# brd.net
KiCad netlist of a schematic drawn in EAGLE
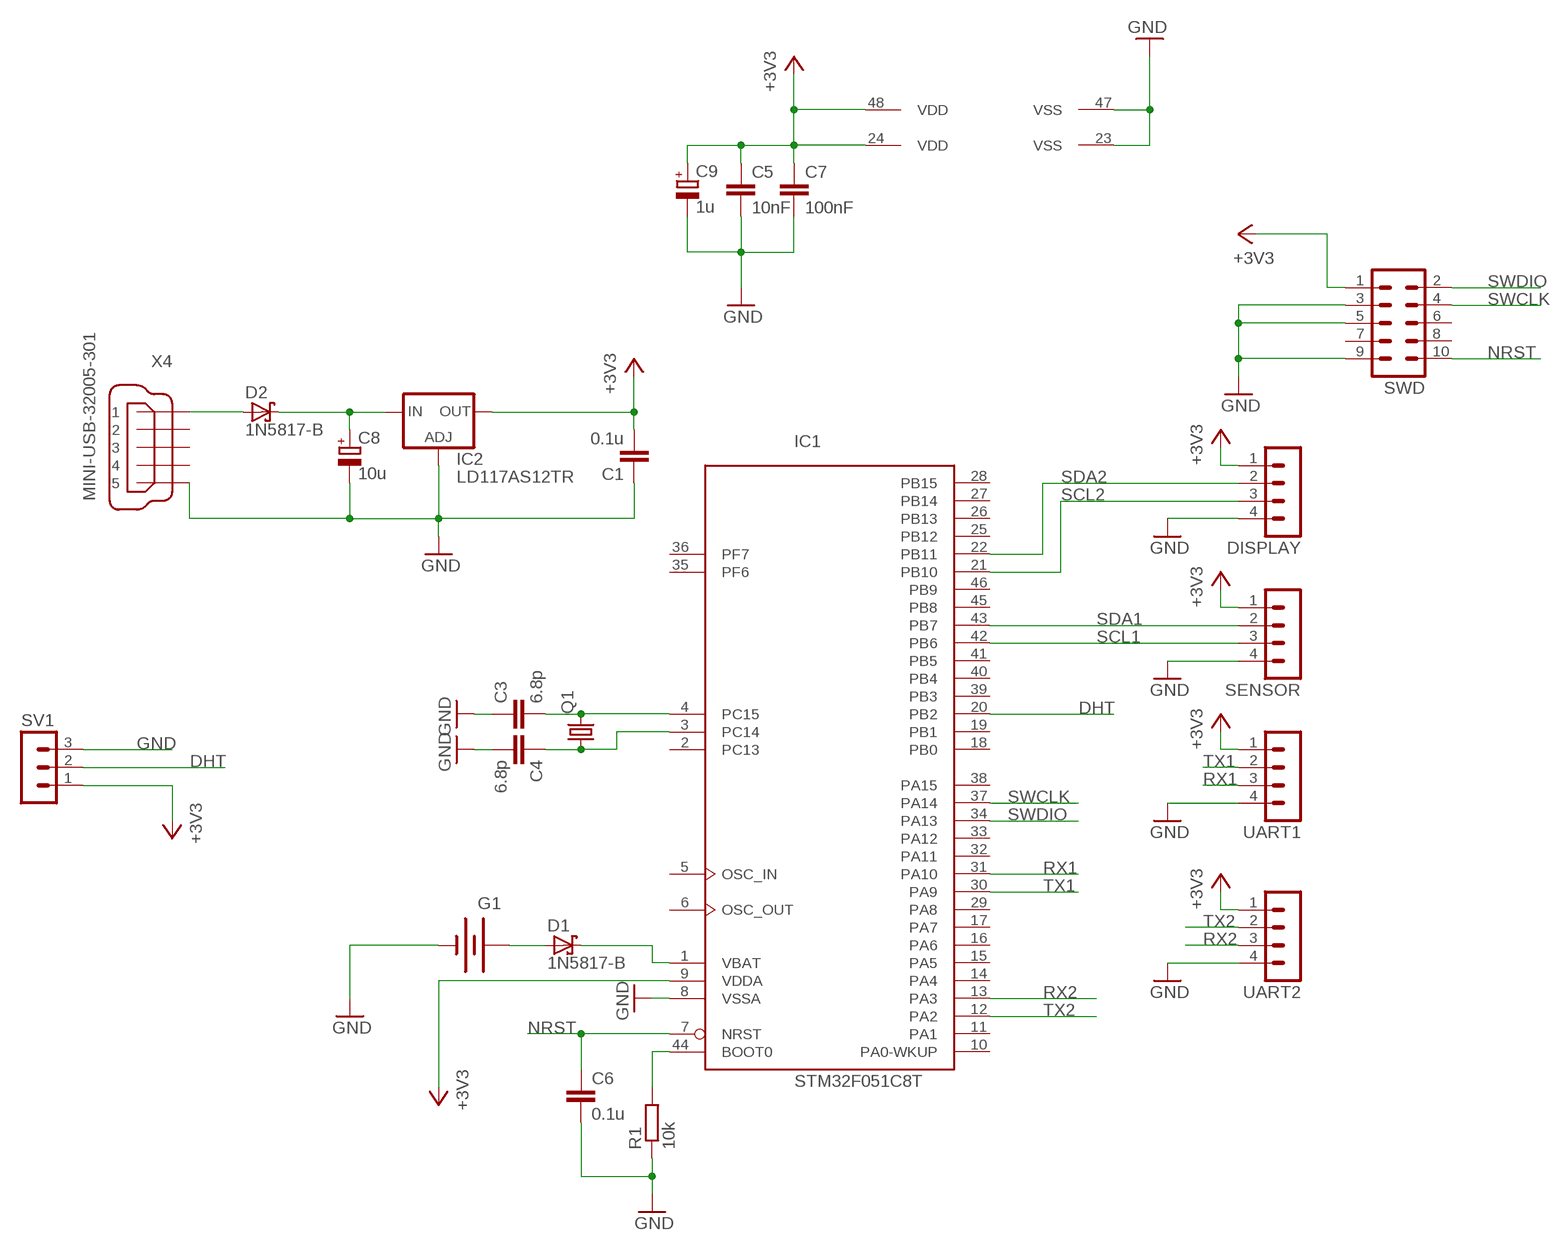
[diagram p0: schematic, sheet 1]

(export (version "E")
  (design (tool "Eeschema 10.0.6"))
  (components
    (comp (ref "C1")
      (value "0.1u")
      (footprint "eagle-import:C025-024X044")
      (libsource (lib "eagle-import") (part "C-EU025-024X044"))
    )
    (comp (ref "C3")
      (value "6.8p")
      (footprint "eagle-import:C0805")
      (libsource (lib "eagle-import") (part "C-EUC0805"))
    )
    (comp (ref "C4")
      (value "6.8p")
      (footprint "eagle-import:C0805")
      (libsource (lib "eagle-import") (part "C-EUC0805"))
    )
    (comp (ref "C5")
      (value "10nF")
      (footprint "eagle-import:C0805")
      (libsource (lib "eagle-import") (part "C-EUC0805"))
    )
    (comp (ref "C6")
      (value "0.1u")
      (footprint "eagle-import:C0805")
      (libsource (lib "eagle-import") (part "C-EUC0805"))
    )
    (comp (ref "C7")
      (value "100nF")
      (footprint "eagle-import:C0805")
      (libsource (lib "eagle-import") (part "C-EUC0805"))
    )
    (comp (ref "C8")
      (value "10u")
      (footprint "eagle-import:E2,5-6E")
      (libsource (lib "eagle-import") (part "CPOL-EUE2,5-6E"))
    )
    (comp (ref "C9")
      (value "1u")
      (footprint "eagle-import:E2,5-6E")
      (libsource (lib "eagle-import") (part "CPOL-EUE2,5-6E"))
    )
    (comp (ref "D1")
      (value "1N5817-B")
      (footprint "eagle-import:DO41-7.6")
      (libsource (lib "eagle-import") (part "1N5817-B"))
    )
    (comp (ref "D2")
      (value "1N5817-B")
      (footprint "eagle-import:DO41-7.6")
      (libsource (lib "eagle-import") (part "1N5817-B"))
    )
    (comp (ref "DISPLAY")
      (value "MA04-1")
      (footprint "eagle-import:MA04-1")
      (libsource (lib "eagle-import") (part "MA04-1"))
    )
    (comp (ref "G1")
      (value "BATTERY20PTH")
      (footprint "eagle-import:BATTCOM_20MM_PTH")
      (libsource (lib "eagle-import") (part "BATTERY20PTH"))
    )
    (comp (ref "IC1")
      (value "STM32F051C8T")
      (footprint "eagle-import:LQFP48")
      (libsource (lib "eagle-import") (part "STM32F051CT8"))
    )
    (comp (ref "IC2")
      (value "LD117AS12TR")
      (footprint "eagle-import:SOT223")
      (libsource (lib "eagle-import") (part "LD117A?S12TR"))
    )
    (comp (ref "Q1")
      (value "CRYSTALTC26H")
      (footprint "eagle-import:TC26H")
      (libsource (lib "eagle-import") (part "CRYSTALTC26H"))
    )
    (comp (ref "R1")
      (value "10k")
      (footprint "eagle-import:R0805")
      (libsource (lib "eagle-import") (part "R-EU_R0805"))
    )
    (comp (ref "SENSOR")
      (value "MA04-1")
      (footprint "eagle-import:MA04-1")
      (libsource (lib "eagle-import") (part "MA04-1"))
    )
    (comp (ref "SV1")
      (value "MA03-1")
      (footprint "eagle-import:MA03-1")
      (libsource (lib "eagle-import") (part "MA03-1"))
    )
    (comp (ref "SWD")
      (value "MA05-2")
      (footprint "eagle-import:MA05-2")
      (libsource (lib "eagle-import") (part "MA05-2"))
    )
    (comp (ref "UART1")
      (value "MA04-1")
      (footprint "eagle-import:MA04-1")
      (libsource (lib "eagle-import") (part "MA04-1"))
    )
    (comp (ref "UART2")
      (value "MA04-1")
      (footprint "eagle-import:MA04-1")
      (libsource (lib "eagle-import") (part "MA04-1"))
    )
    (comp (ref "X4")
      (value "MINI-USB-32005-301")
      (footprint "eagle-import:32005-301")
      (libsource (lib "eagle-import") (part "MINI-USB-32005-301"))
    )
  )
  (nets
    (net (code "1") (name "+3V3") (class "Default")
      (node (ref "C1") (pin "2") (pinfunction "2_2") (pintype "passive"))
      (node (ref "C5") (pin "1") (pinfunction "1_1") (pintype "passive"))
      (node (ref "C7") (pin "1") (pinfunction "1_1") (pintype "passive"))
      (node (ref "C9") (pin "+") (pinfunction "+_+") (pintype "passive"))
      (node (ref "DISPLAY") (pin "1") (pinfunction "1_1") (pintype "passive"))
      (node (ref "IC1") (pin "24") (pinfunction "VDD_24") (pintype "power_in"))
      (node (ref "IC1") (pin "48") (pinfunction "VDD_48") (pintype "power_in"))
      (node (ref "IC1") (pin "9") (pinfunction "VDDA_9") (pintype "power_in"))
      (node (ref "IC2") (pin "4") (pinfunction "OUT_4") (pintype "passive"))
      (node (ref "SENSOR") (pin "1") (pinfunction "1_1") (pintype "passive"))
      (node (ref "SV1") (pin "1") (pinfunction "1_1") (pintype "passive"))
      (node (ref "SWD") (pin "1") (pinfunction "1_1") (pintype "passive"))
      (node (ref "UART1") (pin "1") (pinfunction "1_1") (pintype "passive"))
      (node (ref "UART2") (pin "1") (pinfunction "1_1") (pintype "passive"))
    )
    (net (code "2") (name "/DHT") (class "Default")
      (node (ref "IC1") (pin "20") (pinfunction "PB2_20") (pintype "bidirectional"))
      (node (ref "SV1") (pin "2") (pinfunction "2_2") (pintype "passive"))
    )
    (net (code "3") (name "/NRST") (class "Default")
      (node (ref "C6") (pin "1") (pinfunction "1_1") (pintype "passive"))
      (node (ref "IC1") (pin "7") (pinfunction "NRST_7") (pintype "bidirectional"))
      (node (ref "SWD") (pin "10") (pinfunction "10_10") (pintype "passive"))
    )
    (net (code "4") (name "/RX1") (class "Default")
      (node (ref "IC1") (pin "31") (pinfunction "PA10_31") (pintype "bidirectional"))
      (node (ref "UART1") (pin "3") (pinfunction "3_3") (pintype "passive"))
    )
    (net (code "5") (name "/RX2") (class "Default")
      (node (ref "IC1") (pin "13") (pinfunction "PA3_13") (pintype "bidirectional"))
      (node (ref "UART2") (pin "3") (pinfunction "3_3") (pintype "passive"))
    )
    (net (code "6") (name "/SCL1") (class "Default")
      (node (ref "IC1") (pin "42") (pinfunction "PB6_42") (pintype "bidirectional"))
      (node (ref "SENSOR") (pin "3") (pinfunction "3_3") (pintype "passive"))
    )
    (net (code "7") (name "/SCL2") (class "Default")
      (node (ref "DISPLAY") (pin "3") (pinfunction "3_3") (pintype "passive"))
      (node (ref "IC1") (pin "21") (pinfunction "PB10_21") (pintype "bidirectional"))
    )
    (net (code "8") (name "/SDA1") (class "Default")
      (node (ref "IC1") (pin "43") (pinfunction "PB7_43") (pintype "bidirectional"))
      (node (ref "SENSOR") (pin "2") (pinfunction "2_2") (pintype "passive"))
    )
    (net (code "9") (name "/SDA2") (class "Default")
      (node (ref "DISPLAY") (pin "2") (pinfunction "2_2") (pintype "passive"))
      (node (ref "IC1") (pin "22") (pinfunction "PB11_22") (pintype "bidirectional"))
    )
    (net (code "10") (name "/SWCLK") (class "Default")
      (node (ref "IC1") (pin "37") (pinfunction "PA14_37") (pintype "bidirectional"))
      (node (ref "SWD") (pin "4") (pinfunction "4_4") (pintype "passive"))
    )
    (net (code "11") (name "/SWDIO") (class "Default")
      (node (ref "IC1") (pin "34") (pinfunction "PA13_34") (pintype "bidirectional"))
      (node (ref "SWD") (pin "2") (pinfunction "2_2") (pintype "passive"))
    )
    (net (code "12") (name "/TX1") (class "Default")
      (node (ref "IC1") (pin "30") (pinfunction "PA9_30") (pintype "bidirectional"))
      (node (ref "UART1") (pin "2") (pinfunction "2_2") (pintype "passive"))
    )
    (net (code "13") (name "/TX2") (class "Default")
      (node (ref "IC1") (pin "12") (pinfunction "PA2_12") (pintype "bidirectional"))
      (node (ref "UART2") (pin "2") (pinfunction "2_2") (pintype "passive"))
    )
    (net (code "14") (name "GND") (class "Default")
      (node (ref "C1") (pin "1") (pinfunction "1_1") (pintype "passive"))
      (node (ref "C3") (pin "1") (pinfunction "1_1") (pintype "passive"))
      (node (ref "C4") (pin "2") (pinfunction "2_2") (pintype "passive"))
      (node (ref "C5") (pin "2") (pinfunction "2_2") (pintype "passive"))
      (node (ref "C6") (pin "2") (pinfunction "2_2") (pintype "passive"))
      (node (ref "C7") (pin "2") (pinfunction "2_2") (pintype "passive"))
      (node (ref "C8") (pin "-") (pinfunction "-_-") (pintype "passive"))
      (node (ref "C9") (pin "-") (pinfunction "-_-") (pintype "passive"))
      (node (ref "DISPLAY") (pin "4") (pinfunction "4_4") (pintype "passive"))
      (node (ref "G1") (pin "2") (pinfunction "-_2") (pintype "power_in"))
      (node (ref "IC1") (pin "23") (pinfunction "VSS_23") (pintype "power_in"))
      (node (ref "IC1") (pin "47") (pinfunction "VSS_47") (pintype "power_in"))
      (node (ref "IC1") (pin "8") (pinfunction "VSSA_8") (pintype "power_in"))
      (node (ref "IC2") (pin "1") (pinfunction "ADJ_1") (pintype "input"))
      (node (ref "R1") (pin "1") (pinfunction "1_1") (pintype "passive"))
      (node (ref "SENSOR") (pin "4") (pinfunction "4_4") (pintype "passive"))
      (node (ref "SV1") (pin "3") (pinfunction "3_3") (pintype "passive"))
      (node (ref "SWD") (pin "3") (pinfunction "3_3") (pintype "passive"))
      (node (ref "SWD") (pin "5") (pinfunction "5_5") (pintype "passive"))
      (node (ref "SWD") (pin "9") (pinfunction "9_9") (pintype "passive"))
      (node (ref "UART1") (pin "4") (pinfunction "4_4") (pintype "passive"))
      (node (ref "UART2") (pin "4") (pinfunction "4_4") (pintype "passive"))
      (node (ref "X4") (pin "5") (pinfunction "5_5") (pintype "passive"))
    )
    (net (code "15") (name "Net-(D2-PadA)") (class "Default")
      (node (ref "D2") (pin "A") (pinfunction "A_A") (pintype "passive"))
      (node (ref "X4") (pin "1") (pinfunction "1_1") (pintype "passive"))
    )
    (net (code "16") (name "Net-(G1-+)") (class "Default")
      (node (ref "D1") (pin "A") (pinfunction "A_A") (pintype "passive"))
      (node (ref "G1") (pin "1") (pinfunction "+_1") (pintype "power_in"))
    )
    (net (code "17") (name "Net-(IC1A-BOOT0)") (class "Default")
      (node (ref "IC1") (pin "44") (pinfunction "BOOT0_44") (pintype "input"))
      (node (ref "R1") (pin "2") (pinfunction "2_2") (pintype "passive"))
    )
    (net (code "18") (name "Net-(IC1A-PC14)") (class "Default")
      (node (ref "C4") (pin "1") (pinfunction "1_1") (pintype "passive"))
      (node (ref "IC1") (pin "3") (pinfunction "PC14_3") (pintype "bidirectional"))
      (node (ref "Q1") (pin "1") (pinfunction "1_1") (pintype "passive"))
    )
    (net (code "19") (name "Net-(IC1A-PC15)") (class "Default")
      (node (ref "C3") (pin "2") (pinfunction "2_2") (pintype "passive"))
      (node (ref "IC1") (pin "4") (pinfunction "PC15_4") (pintype "bidirectional"))
      (node (ref "Q1") (pin "2") (pinfunction "2_2") (pintype "passive"))
    )
    (net (code "20") (name "Net-(IC1A-VBAT)") (class "Default")
      (node (ref "D1") (pin "C") (pinfunction "C_C") (pintype "passive"))
      (node (ref "IC1") (pin "1") (pinfunction "VBAT_1") (pintype "power_in"))
    )
    (net (code "21") (name "Net-(IC2-IN)") (class "Default")
      (node (ref "C8") (pin "+") (pinfunction "+_+") (pintype "passive"))
      (node (ref "D2") (pin "C") (pinfunction "C_C") (pintype "passive"))
      (node (ref "IC2") (pin "3") (pinfunction "IN_3") (pintype "input"))
    )
    (net (code "22") (name "unconnected-(IC1A-OSC_IN-Pad5)") (class "Default")
      (node (ref "IC1") (pin "5") (pinfunction "OSC_IN_5") (pintype "bidirectional"))
    )
    (net (code "23") (name "unconnected-(IC1A-OSC_OUT-Pad6)") (class "Default")
      (node (ref "IC1") (pin "6") (pinfunction "OSC_OUT_6") (pintype "bidirectional"))
    )
    (net (code "24") (name "unconnected-(IC1A-PA0-WKUP-Pad10)") (class "Default")
      (node (ref "IC1") (pin "10") (pinfunction "PA0-WKUP_10") (pintype "bidirectional"))
    )
    (net (code "25") (name "unconnected-(IC1A-PA1-Pad11)") (class "Default")
      (node (ref "IC1") (pin "11") (pinfunction "PA1_11") (pintype "bidirectional"))
    )
    (net (code "26") (name "unconnected-(IC1A-PA4-Pad14)") (class "Default")
      (node (ref "IC1") (pin "14") (pinfunction "PA4_14") (pintype "bidirectional"))
    )
    (net (code "27") (name "unconnected-(IC1A-PA5-Pad15)") (class "Default")
      (node (ref "IC1") (pin "15") (pinfunction "PA5_15") (pintype "bidirectional"))
    )
    (net (code "28") (name "unconnected-(IC1A-PA6-Pad16)") (class "Default")
      (node (ref "IC1") (pin "16") (pinfunction "PA6_16") (pintype "bidirectional"))
    )
    (net (code "29") (name "unconnected-(IC1A-PA7-Pad17)") (class "Default")
      (node (ref "IC1") (pin "17") (pinfunction "PA7_17") (pintype "bidirectional"))
    )
    (net (code "30") (name "unconnected-(IC1A-PA8-Pad29)") (class "Default")
      (node (ref "IC1") (pin "29") (pinfunction "PA8_29") (pintype "bidirectional"))
    )
    (net (code "31") (name "unconnected-(IC1A-PA11-Pad32)") (class "Default")
      (node (ref "IC1") (pin "32") (pinfunction "PA11_32") (pintype "bidirectional"))
    )
    (net (code "32") (name "unconnected-(IC1A-PA12-Pad33)") (class "Default")
      (node (ref "IC1") (pin "33") (pinfunction "PA12_33") (pintype "bidirectional"))
    )
    (net (code "33") (name "unconnected-(IC1A-PA15-Pad38)") (class "Default")
      (node (ref "IC1") (pin "38") (pinfunction "PA15_38") (pintype "bidirectional"))
    )
    (net (code "34") (name "unconnected-(IC1A-PB0-Pad18)") (class "Default")
      (node (ref "IC1") (pin "18") (pinfunction "PB0_18") (pintype "bidirectional"))
    )
    (net (code "35") (name "unconnected-(IC1A-PB1-Pad19)") (class "Default")
      (node (ref "IC1") (pin "19") (pinfunction "PB1_19") (pintype "bidirectional"))
    )
    (net (code "36") (name "unconnected-(IC1A-PB3-Pad39)") (class "Default")
      (node (ref "IC1") (pin "39") (pinfunction "PB3_39") (pintype "bidirectional"))
    )
    (net (code "37") (name "unconnected-(IC1A-PB4-Pad40)") (class "Default")
      (node (ref "IC1") (pin "40") (pinfunction "PB4_40") (pintype "bidirectional"))
    )
    (net (code "38") (name "unconnected-(IC1A-PB5-Pad41)") (class "Default")
      (node (ref "IC1") (pin "41") (pinfunction "PB5_41") (pintype "bidirectional"))
    )
    (net (code "39") (name "unconnected-(IC1A-PB8-Pad45)") (class "Default")
      (node (ref "IC1") (pin "45") (pinfunction "PB8_45") (pintype "bidirectional"))
    )
    (net (code "40") (name "unconnected-(IC1A-PB9-Pad46)") (class "Default")
      (node (ref "IC1") (pin "46") (pinfunction "PB9_46") (pintype "bidirectional"))
    )
    (net (code "41") (name "unconnected-(IC1A-PB12-Pad25)") (class "Default")
      (node (ref "IC1") (pin "25") (pinfunction "PB12_25") (pintype "bidirectional"))
    )
    (net (code "42") (name "unconnected-(IC1A-PB13-Pad26)") (class "Default")
      (node (ref "IC1") (pin "26") (pinfunction "PB13_26") (pintype "bidirectional"))
    )
    (net (code "43") (name "unconnected-(IC1A-PB14-Pad27)") (class "Default")
      (node (ref "IC1") (pin "27") (pinfunction "PB14_27") (pintype "bidirectional"))
    )
    (net (code "44") (name "unconnected-(IC1A-PB15-Pad28)") (class "Default")
      (node (ref "IC1") (pin "28") (pinfunction "PB15_28") (pintype "bidirectional"))
    )
    (net (code "45") (name "unconnected-(IC1A-PC13-Pad2)") (class "Default")
      (node (ref "IC1") (pin "2") (pinfunction "PC13_2") (pintype "bidirectional"))
    )
    (net (code "46") (name "unconnected-(IC1A-PF6-Pad35)") (class "Default")
      (node (ref "IC1") (pin "35") (pinfunction "PF6_35") (pintype "bidirectional"))
    )
    (net (code "47") (name "unconnected-(IC1A-PF7-Pad36)") (class "Default")
      (node (ref "IC1") (pin "36") (pinfunction "PF7_36") (pintype "bidirectional"))
    )
    (net (code "48") (name "unconnected-(SWD-Pad6)") (class "Default")
      (node (ref "SWD") (pin "6") (pinfunction "6_6") (pintype "passive"))
    )
    (net (code "49") (name "unconnected-(SWD-Pad7)") (class "Default")
      (node (ref "SWD") (pin "7") (pinfunction "7_7") (pintype "passive"))
    )
    (net (code "50") (name "unconnected-(SWD-Pad8)") (class "Default")
      (node (ref "SWD") (pin "8") (pinfunction "8_8") (pintype "passive"))
    )
    (net (code "51") (name "unconnected-(X4-Pad2)") (class "Default")
      (node (ref "X4") (pin "2") (pinfunction "2_2") (pintype "passive"))
    )
    (net (code "52") (name "unconnected-(X4-Pad3)") (class "Default")
      (node (ref "X4") (pin "3") (pinfunction "3_3") (pintype "passive"))
    )
    (net (code "53") (name "unconnected-(X4-Pad4)") (class "Default")
      (node (ref "X4") (pin "4") (pinfunction "4_4") (pintype "passive"))
    )
  )
)
